# Display_LED.net
KiCad netlist of a schematic drawn in Altium Designer
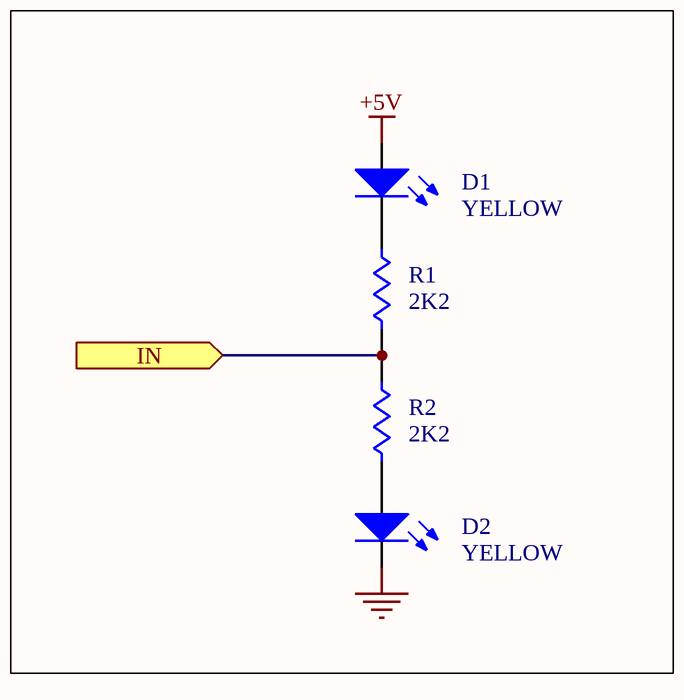
[diagram p0: Display_LED.SchDoc]

(export (version "E")
  (design (tool "Eeschema 10.0.6"))
  (components
    (comp (ref "D1")
      (value "YELLOW")
      (footprint "0805_Diode")
      (description "Typical INFRARED GaAs LED")
      (fields (field (name "MANUFACTURER") "Generic Components") (field (name "PUBLISHER") "Altium Limited"))
      (libsource (lib "my Libraries") (part "Optical Transmitter"))
    )
    (comp (ref "D2")
      (value "YELLOW")
      (footprint "0805_Diode")
      (description "Typical INFRARED GaAs LED")
      (fields (field (name "MANUFACTURER") "Generic Components") (field (name "PUBLISHER") "Altium Limited"))
      (libsource (lib "my Libraries") (part "Optical Transmitter"))
    )
    (comp (ref "R1")
      (value "2K2")
      (footprint "0805")
      (description "Resistor")
      (fields (field (name "MANUFACTURER") "Generic Components") (field (name "PUBLISHER") "Altium Limited"))
      (libsource (lib "Miscellaneous Devices") (part "Res1"))
    )
    (comp (ref "R2")
      (value "2K2")
      (footprint "0805")
      (description "Resistor")
      (fields (field (name "MANUFACTURER") "Generic Components") (field (name "PUBLISHER") "Altium Limited"))
      (libsource (lib "Miscellaneous Devices") (part "Res1"))
    )
  )
  (nets
    (net (code "1") (name "+5V") (class "Default")
      (node (ref "D1") (pin "1") (pinfunction "A_1") (pintype "passive"))
    )
    (net (code "2") (name "/IN") (class "Default")
      (node (ref "R1") (pin "1") (pinfunction "1_1") (pintype "passive"))
      (node (ref "R2") (pin "2") (pinfunction "2_2") (pintype "passive"))
    )
    (net (code "3") (name "GND") (class "Default")
      (node (ref "D2") (pin "2") (pinfunction "K_2") (pintype "passive"))
    )
    (net (code "4") (name "Net-(D1-K)") (class "Default")
      (node (ref "D1") (pin "2") (pinfunction "K_2") (pintype "passive"))
      (node (ref "R1") (pin "2") (pinfunction "2_2") (pintype "passive"))
    )
    (net (code "5") (name "Net-(D2-A)") (class "Default")
      (node (ref "D2") (pin "1") (pinfunction "A_1") (pintype "passive"))
      (node (ref "R2") (pin "1") (pinfunction "1_1") (pintype "passive"))
    )
  )
)
